# STM32F1.net
KiCad netlist of a schematic drawn in Altium Designer
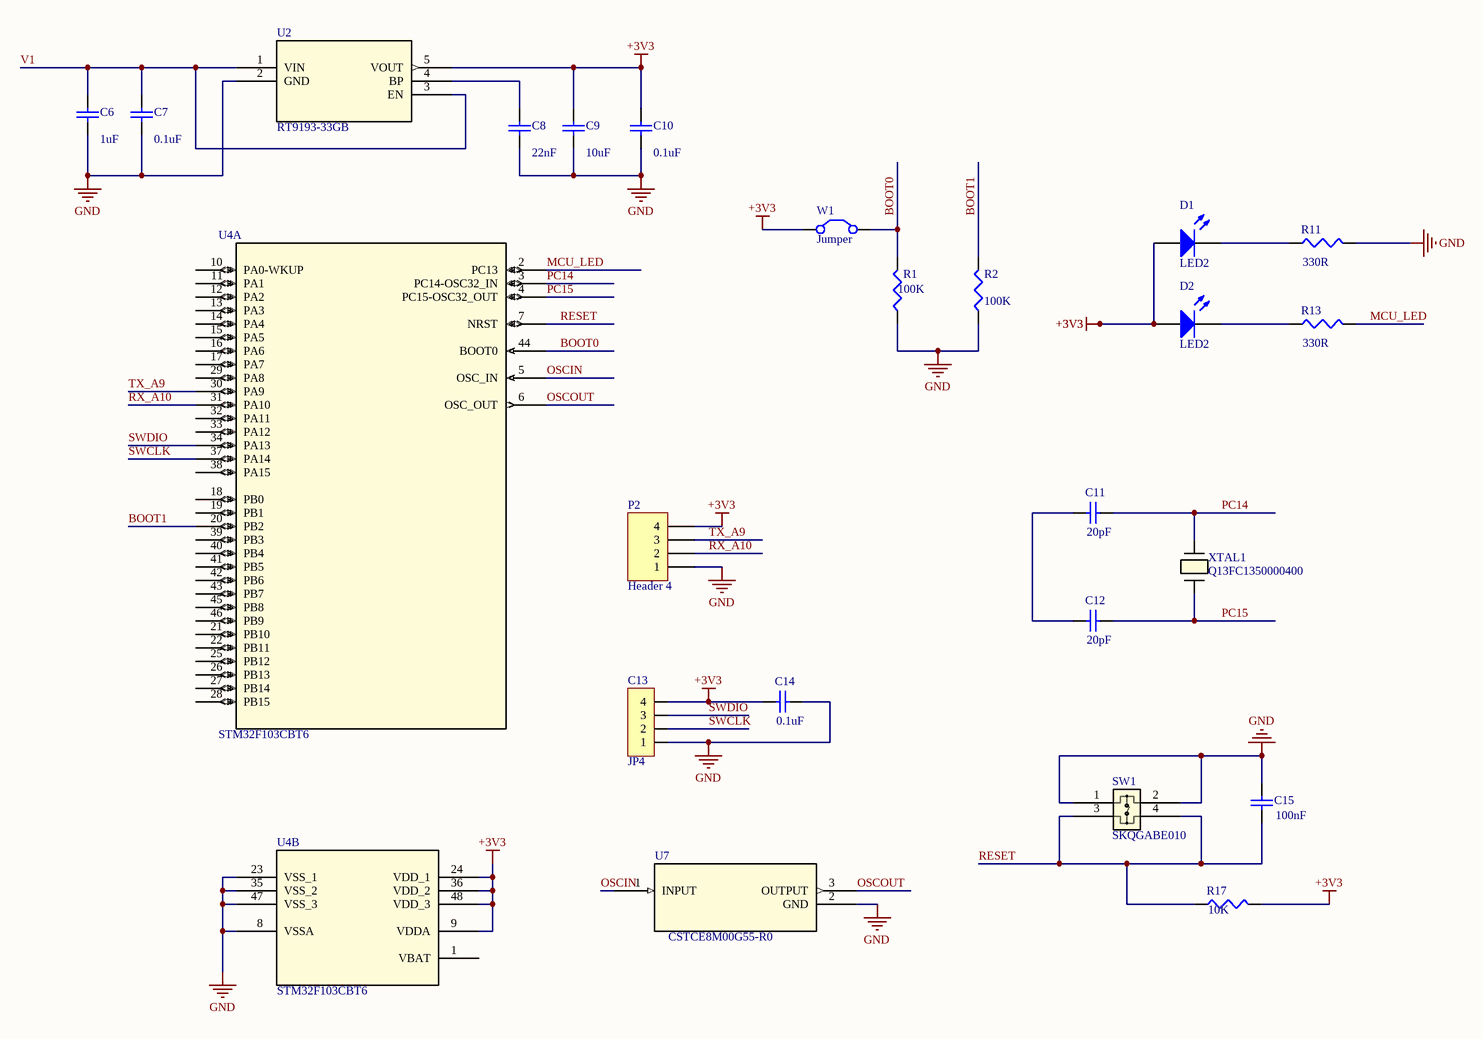
[diagram p0: STM32F1.SchDoc]

(export (version "E")
  (design (tool "Eeschema 10.0.6"))
  (components
    (comp (ref "C6")
      (value "1uF")
      (footprint "RAD-0.3")
      (description "Capacitor")
      (fields (field (name "PUBLISHER") "Altium Limited"))
      (libsource (lib "Miscellaneous Devices") (part "Cap"))
    )
    (comp (ref "C7")
      (value "0.1uF")
      (footprint "RAD-0.3")
      (description "Capacitor")
      (fields (field (name "PUBLISHER") "Altium Limited"))
      (libsource (lib "Miscellaneous Devices") (part "Cap"))
    )
    (comp (ref "C8")
      (value "22nF")
      (footprint "RAD-0.3")
      (description "Capacitor")
      (fields (field (name "PUBLISHER") "Altium Limited"))
      (libsource (lib "Miscellaneous Devices") (part "Cap"))
    )
    (comp (ref "C9")
      (value "10uF")
      (footprint "RAD-0.3")
      (description "Capacitor")
      (fields (field (name "PUBLISHER") "Altium Limited"))
      (libsource (lib "Miscellaneous Devices") (part "Cap"))
    )
    (comp (ref "C10")
      (value "0.1uF")
      (footprint "RAD-0.3")
      (description "Capacitor")
      (fields (field (name "PUBLISHER") "Altium Limited"))
      (libsource (lib "Miscellaneous Devices") (part "Cap"))
    )
    (comp (ref "C11")
      (value "20pF")
      (footprint "RAD-0.3")
      (description "Capacitor")
      (fields (field (name "PUBLISHER") "Altium Limited"))
      (libsource (lib "Miscellaneous Devices") (part "Cap"))
    )
    (comp (ref "C12")
      (value "20pF")
      (footprint "RAD-0.3")
      (description "Capacitor")
      (fields (field (name "PUBLISHER") "Altium Limited"))
      (libsource (lib "Miscellaneous Devices") (part "Cap"))
    )
    (comp (ref "C13")
      (value "JP4")
      (footprint "JP4-C1T")
      (description "WR-PHD 2.54 mm Angled Socket Header")
      (fields
        (field (name "MANUFACTURER") "Würth Elektronik eiSos GmbH")
        (field (name "PARTNO") "613004143121")
        (field (name "CREATED BY") "Karrer Zheng")
      )
      (libsource (lib "My Library") (part "JP4"))
    )
    (comp (ref "C14")
      (value "0.1uF")
      (footprint "RAD-0.3")
      (description "Capacitor")
      (fields (field (name "PUBLISHER") "Altium Limited"))
      (libsource (lib "Miscellaneous Devices") (part "Cap"))
    )
    (comp (ref "C15")
      (value "100nF")
      (footprint "RAD-0.3")
      (description "Capacitor")
      (fields (field (name "PUBLISHER") "Altium Limited"))
      (libsource (lib "Miscellaneous Devices") (part "Cap"))
    )
    (comp (ref "D1")
      (value "LED2")
      (footprint "3.2X1.6X1.1")
      (description "Typical RED, GREEN, YELLOW, AMBER GaAs LED")
      (fields (field (name "PUBLISHER") "Altium Limited"))
      (libsource (lib "Miscellaneous Devices") (part "LED2"))
    )
    (comp (ref "D2")
      (value "LED2")
      (footprint "3.2X1.6X1.1")
      (description "Typical RED, GREEN, YELLOW, AMBER GaAs LED")
      (fields (field (name "PUBLISHER") "Altium Limited"))
      (libsource (lib "Miscellaneous Devices") (part "LED2"))
    )
    (comp (ref "P2")
      (value "Header 4")
      (footprint "HDR1X4")
      (description "Header, 4-Pin")
      (fields (field (name "PUBLISHER") "Altium Limited"))
      (libsource (lib "Miscellaneous Connectors") (part "Header 4"))
    )
    (comp (ref "R1")
      (value "100K")
      (footprint "J1-0603")
      (description "Resistor")
      (fields (field (name "PUBLISHER") "Altium Limited"))
      (libsource (lib "Miscellaneous Devices") (part "Res3"))
    )
    (comp (ref "R2")
      (value "100K")
      (footprint "J1-0603")
      (description "Resistor")
      (fields (field (name "PUBLISHER") "Altium Limited"))
      (libsource (lib "Miscellaneous Devices") (part "Res3"))
    )
    (comp (ref "R11")
      (value "330R")
      (footprint "J1-0603")
      (description "Resistor")
      (fields (field (name "PUBLISHER") "Altium Limited"))
      (libsource (lib "Miscellaneous Devices") (part "Res3"))
    )
    (comp (ref "R13")
      (value "330R")
      (footprint "J1-0603")
      (description "Resistor")
      (fields (field (name "PUBLISHER") "Altium Limited"))
      (libsource (lib "Miscellaneous Devices") (part "Res3"))
    )
    (comp (ref "R17")
      (value "10K")
      (footprint "J1-0603")
      (description "Resistor")
      (fields (field (name "PUBLISHER") "Altium Limited"))
      (libsource (lib "Miscellaneous Devices") (part "Res3"))
    )
    (comp (ref "SW1")
      (value "SKQGABE010")
      (footprint "SKQGABE010_ALPS")
      (description "No Description Available")
      (libsource (lib "SKQGABE010") (part "SKQGABE010"))
    )
    (comp (ref "U2")
      (value "RT9193-33GB")
      (footprint "SOT-23-5_RIT")
      (description "No Description Available")
      (libsource (lib "RT9193-33GB") (part "RT9193-33GB"))
    )
    (comp (ref "U4")
      (value "STM32F103CBT6")
      (footprint "LQFP48-7x7mm")
      (description "No Description Available")
      (libsource (lib "STM32F103CBT6") (part "STM32F103CBT6"))
    )
    (comp (ref "U7")
      (value "CSTCE8M00G55-R0")
      (footprint "CSTCE8M00G55-R0_MUR")
      (description "No Description Available")
      (libsource (lib "CSTCE8M00G55-R0") (part "CSTCE8M00G55-R0"))
    )
    (comp (ref "W1")
      (value "Jumper")
      (footprint "RAD-0.2")
      (description "Jumper Wire")
      (fields (field (name "PUBLISHER") "Altium Limited"))
      (libsource (lib "Miscellaneous Devices") (part "Jumper"))
    )
    (comp (ref "XTAL1")
      (value "Q13FC1350000400")
      (footprint "XTAL_FC-135_EPS")
      (description "No Description Available")
      (libsource (lib "Q13FC1350000400") (part "Q13FC1350000400"))
    )
  )
  (nets
    (net (code "1") (name "+3V3") (class "Default")
      (node (ref "C10") (pin "2") (pinfunction "2_2") (pintype "passive"))
      (node (ref "C13") (pin "4") (pinfunction "4_4") (pintype "passive"))
      (node (ref "C14") (pin "1") (pinfunction "1_1") (pintype "passive"))
      (node (ref "C9") (pin "2") (pinfunction "2_2") (pintype "passive"))
      (node (ref "D1") (pin "1") (pinfunction "A_1") (pintype "passive"))
      (node (ref "D2") (pin "1") (pinfunction "A_1") (pintype "passive"))
      (node (ref "P2") (pin "4") (pinfunction "4_4") (pintype "passive"))
      (node (ref "R17") (pin "2") (pinfunction "2_2") (pintype "passive"))
      (node (ref "U2") (pin "5") (pinfunction "VOUT_5") (pintype "output"))
      (node (ref "U4") (pin "24") (pinfunction "VDD_1_24") (pintype "power_in"))
      (node (ref "U4") (pin "36") (pinfunction "VDD_2_36") (pintype "power_in"))
      (node (ref "U4") (pin "48") (pinfunction "VDD_3_48") (pintype "power_in"))
      (node (ref "U4") (pin "9") (pinfunction "VDDA_9") (pintype "power_in"))
      (node (ref "W1") (pin "1") (pinfunction "C1_1") (pintype "passive"))
    )
    (net (code "2") (name "/BOOT0") (class "Default")
      (node (ref "R1") (pin "2") (pinfunction "2_2") (pintype "passive"))
      (node (ref "U4") (pin "44") (pinfunction "BOOT0_44") (pintype "input"))
      (node (ref "W1") (pin "2") (pinfunction "C2_2") (pintype "passive"))
    )
    (net (code "3") (name "/BOOT1") (class "Default")
      (node (ref "R2") (pin "2") (pinfunction "2_2") (pintype "passive"))
      (node (ref "U4") (pin "20") (pinfunction "PB2_20") (pintype "bidirectional"))
    )
    (net (code "4") (name "/MCU_LED") (class "Default")
      (node (ref "R13") (pin "2") (pinfunction "2_2") (pintype "passive"))
      (node (ref "U4") (pin "2") (pinfunction "PC13_2") (pintype "bidirectional"))
    )
    (net (code "5") (name "/OSCIN") (class "Default")
      (node (ref "U4") (pin "5") (pinfunction "OSC_IN_5") (pintype "input"))
      (node (ref "U7") (pin "1") (pinfunction "INPUT_1") (pintype "input"))
    )
    (net (code "6") (name "/OSCOUT") (class "Default")
      (node (ref "U4") (pin "6") (pinfunction "OSC_OUT_6") (pintype "output"))
      (node (ref "U7") (pin "3") (pinfunction "OUTPUT_3") (pintype "output"))
    )
    (net (code "7") (name "/PC14") (class "Default")
      (node (ref "C11") (pin "2") (pinfunction "2_2") (pintype "passive"))
      (node (ref "U4") (pin "3") (pinfunction "PC14-OSC32_IN_3") (pintype "bidirectional"))
      (node (ref "XTAL1") (pin "2") (pinfunction "2_2") (pintype "passive"))
    )
    (net (code "8") (name "/PC15") (class "Default")
      (node (ref "C12") (pin "2") (pinfunction "2_2") (pintype "passive"))
      (node (ref "U4") (pin "4") (pinfunction "PC15-OSC32_OUT_4") (pintype "bidirectional"))
      (node (ref "XTAL1") (pin "1") (pinfunction "1_1") (pintype "passive"))
    )
    (net (code "9") (name "/RESET") (class "Default")
      (node (ref "C15") (pin "2") (pinfunction "2_2") (pintype "passive"))
      (node (ref "R17") (pin "1") (pinfunction "1_1") (pintype "passive"))
      (node (ref "SW1") (pin "3") (pinfunction "3_3") (pintype "passive"))
      (node (ref "SW1") (pin "4") (pinfunction "4_4") (pintype "passive"))
      (node (ref "U4") (pin "7") (pinfunction "NRST_7") (pintype "bidirectional"))
    )
    (net (code "10") (name "/RX_A10") (class "Default")
      (node (ref "P2") (pin "2") (pinfunction "2_2") (pintype "passive"))
      (node (ref "U4") (pin "31") (pinfunction "PA10_31") (pintype "bidirectional"))
    )
    (net (code "11") (name "/SWCLK") (class "Default")
      (node (ref "C13") (pin "2") (pinfunction "2_2") (pintype "passive"))
      (node (ref "U4") (pin "37") (pinfunction "PA14_37") (pintype "bidirectional"))
    )
    (net (code "12") (name "/SWDIO") (class "Default")
      (node (ref "C13") (pin "3") (pinfunction "3_3") (pintype "passive"))
      (node (ref "U4") (pin "34") (pinfunction "PA13_34") (pintype "bidirectional"))
    )
    (net (code "13") (name "/TX_A9") (class "Default")
      (node (ref "P2") (pin "3") (pinfunction "3_3") (pintype "passive"))
      (node (ref "U4") (pin "30") (pinfunction "PA9_30") (pintype "bidirectional"))
    )
    (net (code "14") (name "/V1") (class "Default")
      (node (ref "C6") (pin "2") (pinfunction "2_2") (pintype "passive"))
      (node (ref "C7") (pin "2") (pinfunction "2_2") (pintype "passive"))
      (node (ref "U2") (pin "1") (pinfunction "VIN_1") (pintype "power_in"))
      (node (ref "U2") (pin "3") (pinfunction "EN_3") (pintype "passive"))
    )
    (net (code "15") (name "GND") (class "Default")
      (node (ref "C10") (pin "1") (pinfunction "1_1") (pintype "passive"))
      (node (ref "C13") (pin "1") (pinfunction "1_1") (pintype "passive"))
      (node (ref "C14") (pin "2") (pinfunction "2_2") (pintype "passive"))
      (node (ref "C15") (pin "1") (pinfunction "1_1") (pintype "passive"))
      (node (ref "C6") (pin "1") (pinfunction "1_1") (pintype "passive"))
      (node (ref "C7") (pin "1") (pinfunction "1_1") (pintype "passive"))
      (node (ref "C8") (pin "1") (pinfunction "1_1") (pintype "passive"))
      (node (ref "C9") (pin "1") (pinfunction "1_1") (pintype "passive"))
      (node (ref "P2") (pin "1") (pinfunction "1_1") (pintype "passive"))
      (node (ref "R1") (pin "1") (pinfunction "1_1") (pintype "passive"))
      (node (ref "R11") (pin "2") (pinfunction "2_2") (pintype "passive"))
      (node (ref "R2") (pin "1") (pinfunction "1_1") (pintype "passive"))
      (node (ref "SW1") (pin "1") (pinfunction "1_1") (pintype "passive"))
      (node (ref "SW1") (pin "2") (pinfunction "2_2") (pintype "passive"))
      (node (ref "U2") (pin "2") (pinfunction "GND_2") (pintype "power_in"))
      (node (ref "U4") (pin "23") (pinfunction "VSS_1_23") (pintype "power_in"))
      (node (ref "U4") (pin "35") (pinfunction "VSS_2_35") (pintype "power_in"))
      (node (ref "U4") (pin "47") (pinfunction "VSS_3_47") (pintype "power_in"))
      (node (ref "U4") (pin "8") (pinfunction "VSSA_8") (pintype "power_in"))
      (node (ref "U7") (pin "2") (pinfunction "GND_2") (pintype "power_in"))
    )
    (net (code "16") (name "Net-(C11-Pad1)") (class "Default")
      (node (ref "C11") (pin "1") (pinfunction "1_1") (pintype "passive"))
      (node (ref "C12") (pin "1") (pinfunction "1_1") (pintype "passive"))
    )
    (net (code "17") (name "Net-(D1-K)") (class "Default")
      (node (ref "D1") (pin "2") (pinfunction "K_2") (pintype "passive"))
      (node (ref "R11") (pin "1") (pinfunction "1_1") (pintype "passive"))
    )
    (net (code "18") (name "Net-(D2-K)") (class "Default")
      (node (ref "D2") (pin "2") (pinfunction "K_2") (pintype "passive"))
      (node (ref "R13") (pin "1") (pinfunction "1_1") (pintype "passive"))
    )
    (net (code "19") (name "Net-(U2-BP)") (class "Default")
      (node (ref "C8") (pin "2") (pinfunction "2_2") (pintype "passive"))
      (node (ref "U2") (pin "4") (pinfunction "BP_4") (pintype "passive"))
    )
    (net (code "20") (name "unconnected-(U4A-PA0-WKUP-Pad10)") (class "Default")
      (node (ref "U4") (pin "10") (pinfunction "PA0-WKUP_10") (pintype "bidirectional"))
    )
    (net (code "21") (name "unconnected-(U4A-PA1-Pad11)") (class "Default")
      (node (ref "U4") (pin "11") (pinfunction "PA1_11") (pintype "bidirectional"))
    )
    (net (code "22") (name "unconnected-(U4A-PA2-Pad12)") (class "Default")
      (node (ref "U4") (pin "12") (pinfunction "PA2_12") (pintype "bidirectional"))
    )
    (net (code "23") (name "unconnected-(U4A-PA3-Pad13)") (class "Default")
      (node (ref "U4") (pin "13") (pinfunction "PA3_13") (pintype "bidirectional"))
    )
    (net (code "24") (name "unconnected-(U4A-PA4-Pad14)") (class "Default")
      (node (ref "U4") (pin "14") (pinfunction "PA4_14") (pintype "bidirectional"))
    )
    (net (code "25") (name "unconnected-(U4A-PA5-Pad15)") (class "Default")
      (node (ref "U4") (pin "15") (pinfunction "PA5_15") (pintype "bidirectional"))
    )
    (net (code "26") (name "unconnected-(U4A-PA6-Pad16)") (class "Default")
      (node (ref "U4") (pin "16") (pinfunction "PA6_16") (pintype "bidirectional"))
    )
    (net (code "27") (name "unconnected-(U4A-PA7-Pad17)") (class "Default")
      (node (ref "U4") (pin "17") (pinfunction "PA7_17") (pintype "bidirectional"))
    )
    (net (code "28") (name "unconnected-(U4A-PA8-Pad29)") (class "Default")
      (node (ref "U4") (pin "29") (pinfunction "PA8_29") (pintype "bidirectional"))
    )
    (net (code "29") (name "unconnected-(U4A-PA11-Pad32)") (class "Default")
      (node (ref "U4") (pin "32") (pinfunction "PA11_32") (pintype "bidirectional"))
    )
    (net (code "30") (name "unconnected-(U4A-PA12-Pad33)") (class "Default")
      (node (ref "U4") (pin "33") (pinfunction "PA12_33") (pintype "bidirectional"))
    )
    (net (code "31") (name "unconnected-(U4A-PA15-Pad38)") (class "Default")
      (node (ref "U4") (pin "38") (pinfunction "PA15_38") (pintype "bidirectional"))
    )
    (net (code "32") (name "unconnected-(U4A-PB0-Pad18)") (class "Default")
      (node (ref "U4") (pin "18") (pinfunction "PB0_18") (pintype "bidirectional"))
    )
    (net (code "33") (name "unconnected-(U4A-PB1-Pad19)") (class "Default")
      (node (ref "U4") (pin "19") (pinfunction "PB1_19") (pintype "bidirectional"))
    )
    (net (code "34") (name "unconnected-(U4A-PB3-Pad39)") (class "Default")
      (node (ref "U4") (pin "39") (pinfunction "PB3_39") (pintype "bidirectional"))
    )
    (net (code "35") (name "unconnected-(U4A-PB4-Pad40)") (class "Default")
      (node (ref "U4") (pin "40") (pinfunction "PB4_40") (pintype "bidirectional"))
    )
    (net (code "36") (name "unconnected-(U4A-PB5-Pad41)") (class "Default")
      (node (ref "U4") (pin "41") (pinfunction "PB5_41") (pintype "bidirectional"))
    )
    (net (code "37") (name "unconnected-(U4A-PB6-Pad42)") (class "Default")
      (node (ref "U4") (pin "42") (pinfunction "PB6_42") (pintype "bidirectional"))
    )
    (net (code "38") (name "unconnected-(U4A-PB7-Pad43)") (class "Default")
      (node (ref "U4") (pin "43") (pinfunction "PB7_43") (pintype "bidirectional"))
    )
    (net (code "39") (name "unconnected-(U4A-PB8-Pad45)") (class "Default")
      (node (ref "U4") (pin "45") (pinfunction "PB8_45") (pintype "bidirectional"))
    )
    (net (code "40") (name "unconnected-(U4A-PB9-Pad46)") (class "Default")
      (node (ref "U4") (pin "46") (pinfunction "PB9_46") (pintype "bidirectional"))
    )
    (net (code "41") (name "unconnected-(U4A-PB10-Pad21)") (class "Default")
      (node (ref "U4") (pin "21") (pinfunction "PB10_21") (pintype "bidirectional"))
    )
    (net (code "42") (name "unconnected-(U4A-PB11-Pad22)") (class "Default")
      (node (ref "U4") (pin "22") (pinfunction "PB11_22") (pintype "bidirectional"))
    )
    (net (code "43") (name "unconnected-(U4A-PB12-Pad25)") (class "Default")
      (node (ref "U4") (pin "25") (pinfunction "PB12_25") (pintype "bidirectional"))
    )
    (net (code "44") (name "unconnected-(U4A-PB13-Pad26)") (class "Default")
      (node (ref "U4") (pin "26") (pinfunction "PB13_26") (pintype "bidirectional"))
    )
    (net (code "45") (name "unconnected-(U4A-PB14-Pad27)") (class "Default")
      (node (ref "U4") (pin "27") (pinfunction "PB14_27") (pintype "bidirectional"))
    )
    (net (code "46") (name "unconnected-(U4A-PB15-Pad28)") (class "Default")
      (node (ref "U4") (pin "28") (pinfunction "PB15_28") (pintype "bidirectional"))
    )
    (net (code "47") (name "unconnected-(U4B-VBAT-Pad1)") (class "Default")
      (node (ref "U4") (pin "1") (pinfunction "VBAT_1") (pintype "power_in"))
    )
  )
)
